# midi.net
KiCad netlist of a schematic drawn in EAGLE
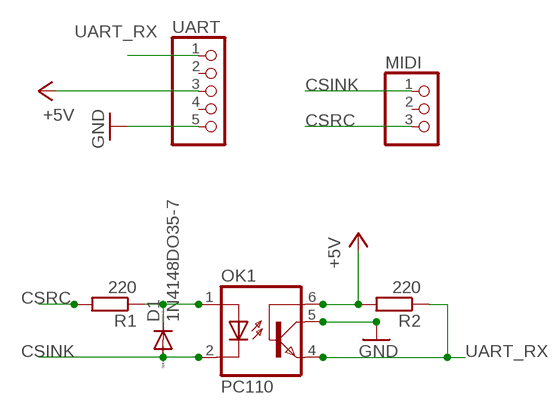
[diagram p0: schematic, sheet 1]

(export (version "E")
  (design (tool "Eeschema 10.0.6"))
  (components
    (comp (ref "D1")
      (value "1N4148DO35-7")
      (footprint "eagle-import:DO35-7")
      (libsource (lib "eagle-import") (part "1N4148DO35-7"))
    )
    (comp (ref "MIDI")
      (value "PINHD-1X3")
      (footprint "eagle-import:1X03")
      (libsource (lib "eagle-import") (part "PINHD-1X3"))
    )
    (comp (ref "OK1")
      (value "PC110")
      (footprint "eagle-import:DIL06")
      (libsource (lib "eagle-import") (part "PC110"))
    )
    (comp (ref "R1")
      (value "220")
      (footprint "eagle-import:0309V")
      (libsource (lib "eagle-import") (part "R-EU_0309/V"))
    )
    (comp (ref "R2")
      (value "220")
      (footprint "eagle-import:0309V")
      (libsource (lib "eagle-import") (part "R-EU_0309/V"))
    )
    (comp (ref "UART")
      (value "PINHD-1X5")
      (footprint "eagle-import:1X05")
      (libsource (lib "eagle-import") (part "PINHD-1X5"))
    )
  )
  (nets
    (net (code "1") (name "+5V") (class "Default")
      (node (ref "OK1") (pin "6") (pinfunction "BAS_6") (pintype "passive"))
      (node (ref "R2") (pin "2") (pinfunction "2_2") (pintype "passive"))
      (node (ref "UART") (pin "3") (pinfunction "3_3") (pintype "passive"))
    )
    (net (code "2") (name "/CSINK") (class "Default")
      (node (ref "D1") (pin "A") (pinfunction "A_A") (pintype "passive"))
      (node (ref "MIDI") (pin "1") (pinfunction "1_1") (pintype "passive"))
      (node (ref "OK1") (pin "2") (pinfunction "C_2") (pintype "passive"))
    )
    (net (code "3") (name "/CSRC") (class "Default")
      (node (ref "MIDI") (pin "3") (pinfunction "3_3") (pintype "passive"))
      (node (ref "R1") (pin "2") (pinfunction "2_2") (pintype "passive"))
    )
    (net (code "4") (name "/UART_RX") (class "Default")
      (node (ref "OK1") (pin "4") (pinfunction "EMI_4") (pintype "passive"))
      (node (ref "R2") (pin "1") (pinfunction "1_1") (pintype "passive"))
      (node (ref "UART") (pin "1") (pinfunction "1_1") (pintype "passive"))
    )
    (net (code "5") (name "GND") (class "Default")
      (node (ref "OK1") (pin "5") (pinfunction "COL_5") (pintype "passive"))
      (node (ref "UART") (pin "5") (pinfunction "5_5") (pintype "passive"))
    )
    (net (code "6") (name "Net-(OK1-A)") (class "Default")
      (node (ref "D1") (pin "C") (pinfunction "C_C") (pintype "passive"))
      (node (ref "OK1") (pin "1") (pinfunction "A_1") (pintype "passive"))
      (node (ref "R1") (pin "1") (pinfunction "1_1") (pintype "passive"))
    )
    (net (code "7") (name "unconnected-(MIDI-Pad2)") (class "Default")
      (node (ref "MIDI") (pin "2") (pinfunction "2_2") (pintype "passive"))
    )
    (net (code "8") (name "unconnected-(UART-Pad2)") (class "Default")
      (node (ref "UART") (pin "2") (pinfunction "2_2") (pintype "passive"))
    )
    (net (code "9") (name "unconnected-(UART-Pad4)") (class "Default")
      (node (ref "UART") (pin "4") (pinfunction "4_4") (pintype "passive"))
    )
  )
)
